# Power_Path_Controllers.net
KiCad netlist of a schematic drawn in Altium Designer
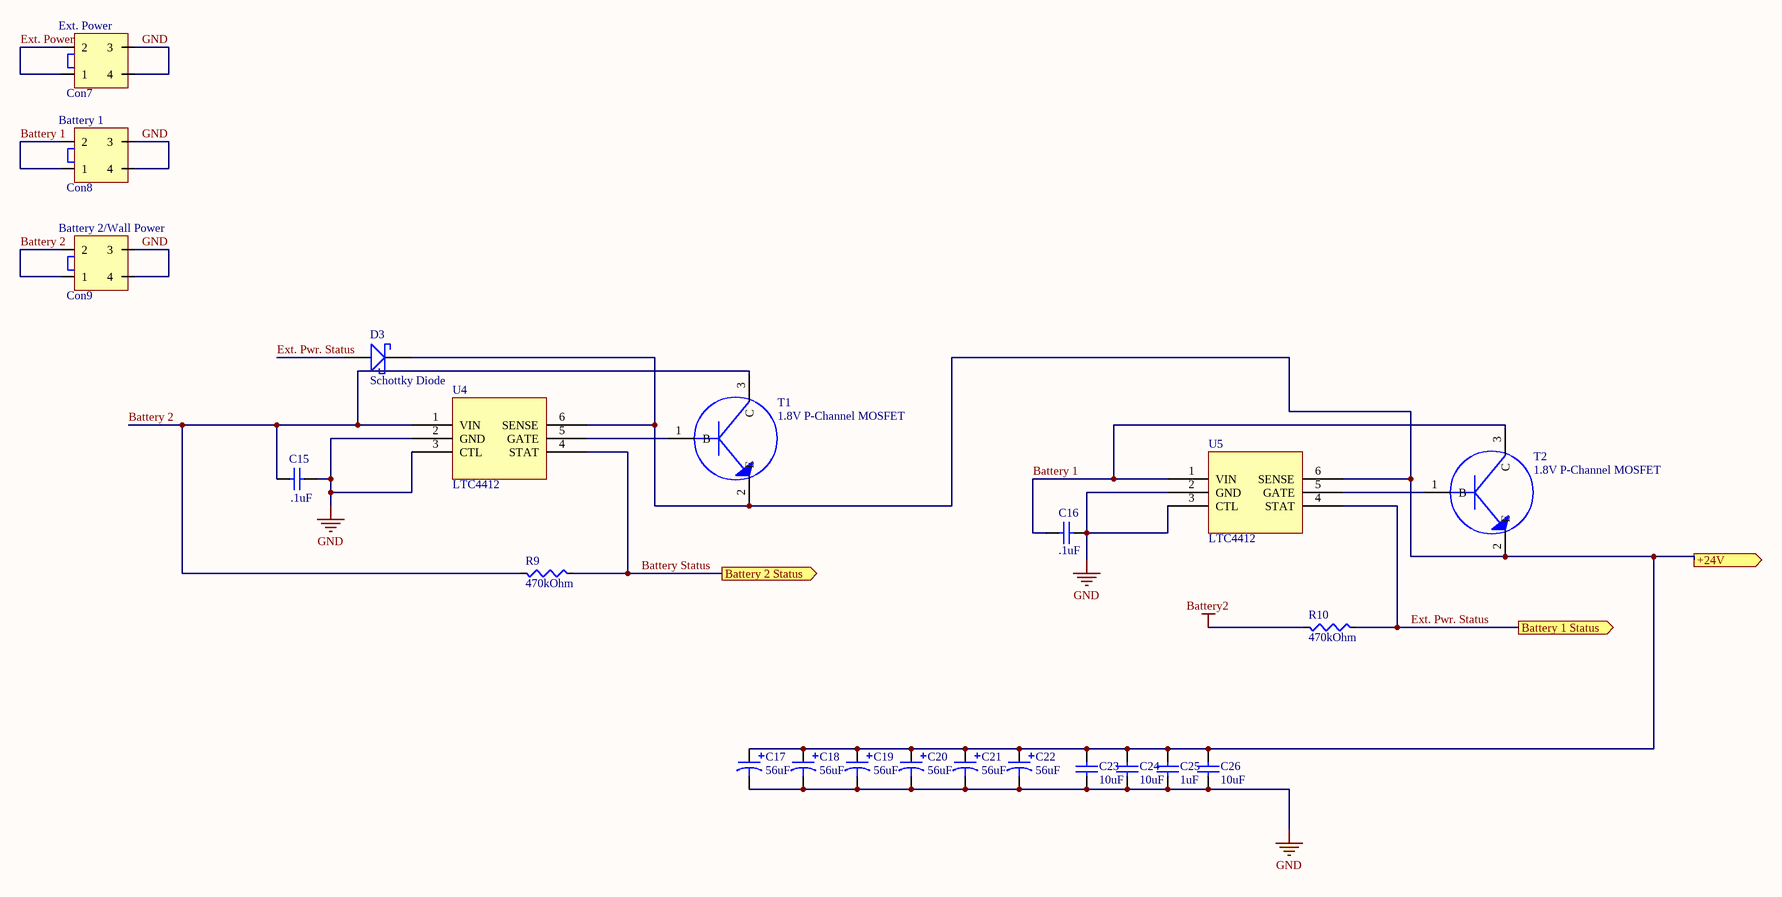
[diagram p0: Power Path Controllers.SchDoc]

(export (version "E")
  (design (tool "Eeschema 10.0.6"))
  (components
    (comp (ref "C15")
      (value ".1uF")
      (footprint "PassiveComponents:0805 (2012) Capacitor")
      (description "Capacitor")
      (libsource (lib "PassiveComponents") (part "Capacitor (non-polarized)"))
    )
    (comp (ref "C16")
      (value ".1uF")
      (footprint "PassiveComponents:0805 (2012) Capacitor")
      (description "Capacitor")
      (libsource (lib "PassiveComponents") (part "Capacitor (non-polarized)"))
    )
    (comp (ref "C17")
      (value "56uF")
      (footprint "PassiveComponents:Radial_8mmDia_SM_E")
      (description "Capacitor (polarized)")
      (libsource (lib "PassiveComponents") (part "Capacitor (polarized)"))
    )
    (comp (ref "C18")
      (value "56uF")
      (footprint "PassiveComponents:Radial_8mmDia_SM_E")
      (description "Capacitor (polarized)")
      (libsource (lib "PassiveComponents") (part "Capacitor (polarized)"))
    )
    (comp (ref "C19")
      (value "56uF")
      (footprint "PassiveComponents:Radial_8mmDia_SM_E")
      (description "Capacitor (polarized)")
      (libsource (lib "PassiveComponents") (part "Capacitor (polarized)"))
    )
    (comp (ref "C20")
      (value "56uF")
      (footprint "PassiveComponents:Radial_8mmDia_SM_E")
      (description "Capacitor (polarized)")
      (libsource (lib "PassiveComponents") (part "Capacitor (polarized)"))
    )
    (comp (ref "C21")
      (value "56uF")
      (footprint "PassiveComponents:Radial_8mmDia_SM_E")
      (description "Capacitor (polarized)")
      (libsource (lib "PassiveComponents") (part "Capacitor (polarized)"))
    )
    (comp (ref "C22")
      (value "56uF")
      (footprint "PassiveComponents:Radial_8mmDia_SM_E")
      (description "Capacitor (polarized)")
      (libsource (lib "PassiveComponents") (part "Capacitor (polarized)"))
    )
    (comp (ref "C23")
      (value "10uF")
      (footprint "PassiveComponents:0805 (2012) Capacitor")
      (description "Capacitor")
      (libsource (lib "PassiveComponents") (part "Capacitor (non-polarized)"))
    )
    (comp (ref "C24")
      (value "10uF")
      (footprint "PassiveComponents:0805 (2012) Capacitor")
      (description "Capacitor")
      (libsource (lib "PassiveComponents") (part "Capacitor (non-polarized)"))
    )
    (comp (ref "C25")
      (value "1uF")
      (footprint "PassiveComponents:0805 (2012) Capacitor")
      (description "Capacitor")
      (libsource (lib "PassiveComponents") (part "Capacitor (non-polarized)"))
    )
    (comp (ref "C26")
      (value "10uF")
      (footprint "PassiveComponents:0805 (2012) Capacitor")
      (description "Capacitor")
      (libsource (lib "PassiveComponents") (part "Capacitor (non-polarized)"))
    )
    (comp (ref "Con7")
      (value "Ext. Power")
      (footprint "Molex:5566-4")
      (libsource (lib "Molex") (part "5566-4"))
    )
    (comp (ref "Con8")
      (value "Battery 1")
      (footprint "Molex:5566-4")
      (libsource (lib "Molex") (part "5566-4"))
    )
    (comp (ref "Con9")
      (value "Battery 2/Wall Power")
      (footprint "Molex:5566-4")
      (libsource (lib "Molex") (part "5566-4"))
    )
    (comp (ref "D3")
      (value "Schottky Diode")
      (footprint "PassiveComponents:DO-41")
      (libsource (lib "PassiveComponents") (part "Schottky Diode"))
    )
    (comp (ref "R9")
      (value "470kOhm")
      (footprint "PassiveComponents:R 0805 (2012) RESISTOR")
      (description "Resistor")
      (libsource (lib "PassiveComponents") (part "Resistor"))
    )
    (comp (ref "R10")
      (value "470kOhm")
      (footprint "PassiveComponents:R 0805 (2012) RESISTOR")
      (description "Resistor")
      (libsource (lib "PassiveComponents") (part "Resistor"))
    )
    (comp (ref "T1")
      (value "1.8V P-Channel MOSFET")
      (footprint "SOT23")
      (libsource (lib "PassiveComponents") (part "Transistor"))
    )
    (comp (ref "T2")
      (value "1.8V P-Channel MOSFET")
      (footprint "SOT23")
      (libsource (lib "PassiveComponents") (part "Transistor"))
    )
    (comp (ref "U4")
      (value "LTC4412")
      (footprint "SOT95P245X110-6N")
      (description "Low Loss Power Path Controller in Thin SOT")
      (libsource (lib "Low Loss Power Path Controller") (part "LTC4412"))
    )
    (comp (ref "U5")
      (value "LTC4412")
      (footprint "SOT95P245X110-6N")
      (description "Low Loss Power Path Controller in Thin SOT")
      (libsource (lib "Low Loss Power Path Controller") (part "LTC4412"))
    )
  )
  (nets
    (net (code "1") (name "/+24V") (class "Default")
      (node (ref "C17") (pin "P") (pinfunction "1_P") (pintype "passive"))
      (node (ref "C18") (pin "P") (pinfunction "1_P") (pintype "passive"))
      (node (ref "C19") (pin "P") (pinfunction "1_P") (pintype "passive"))
      (node (ref "C20") (pin "P") (pinfunction "1_P") (pintype "passive"))
      (node (ref "C21") (pin "P") (pinfunction "1_P") (pintype "passive"))
      (node (ref "C22") (pin "P") (pinfunction "1_P") (pintype "passive"))
      (node (ref "C23") (pin "1") (pinfunction "1_1") (pintype "passive"))
      (node (ref "C24") (pin "1") (pinfunction "1_1") (pintype "passive"))
      (node (ref "C25") (pin "1") (pinfunction "1_1") (pintype "passive"))
      (node (ref "C26") (pin "1") (pinfunction "1_1") (pintype "passive"))
      (node (ref "D3") (pin "K") (pinfunction "K_K") (pintype "passive"))
      (node (ref "T1") (pin "2") (pinfunction "E_2") (pintype "passive"))
      (node (ref "T2") (pin "2") (pinfunction "E_2") (pintype "passive"))
      (node (ref "U4") (pin "6") (pinfunction "SENSE_6") (pintype "passive"))
      (node (ref "U5") (pin "6") (pinfunction "SENSE_6") (pintype "passive"))
    )
    (net (code "2") (name "/Battery 1") (class "Default")
      (node (ref "C16") (pin "1") (pinfunction "1_1") (pintype "passive"))
      (node (ref "Con8") (pin "1") (pinfunction "1_1") (pintype "passive"))
      (node (ref "Con8") (pin "2") (pinfunction "2_2") (pintype "passive"))
      (node (ref "T2") (pin "3") (pinfunction "C_3") (pintype "passive"))
      (node (ref "U5") (pin "1") (pinfunction "VIN_1") (pintype "passive"))
    )
    (net (code "3") (name "/Battery 2") (class "Default")
      (node (ref "C15") (pin "1") (pinfunction "1_1") (pintype "passive"))
      (node (ref "Con9") (pin "1") (pinfunction "1_1") (pintype "passive"))
      (node (ref "Con9") (pin "2") (pinfunction "2_2") (pintype "passive"))
      (node (ref "R9") (pin "2") (pinfunction "2_2") (pintype "passive"))
      (node (ref "T1") (pin "3") (pinfunction "C_3") (pintype "passive"))
      (node (ref "U4") (pin "1") (pinfunction "VIN_1") (pintype "passive"))
    )
    (net (code "4") (name "/Battery Status") (class "Default")
      (node (ref "R9") (pin "1") (pinfunction "1_1") (pintype "passive"))
      (node (ref "U4") (pin "4") (pinfunction "STAT_4") (pintype "passive"))
    )
    (net (code "5") (name "/Ext. Power") (class "Default")
      (node (ref "Con7") (pin "1") (pinfunction "1_1") (pintype "passive"))
      (node (ref "Con7") (pin "2") (pinfunction "2_2") (pintype "passive"))
    )
    (net (code "6") (name "/Ext. Pwr. Status") (class "Default")
      (node (ref "D3") (pin "A") (pinfunction "A_A") (pintype "passive"))
      (node (ref "R10") (pin "1") (pinfunction "1_1") (pintype "passive"))
      (node (ref "U5") (pin "4") (pinfunction "STAT_4") (pintype "passive"))
    )
    (net (code "7") (name "Battery2") (class "Default")
      (node (ref "R10") (pin "2") (pinfunction "2_2") (pintype "passive"))
    )
    (net (code "8") (name "GND") (class "Default")
      (node (ref "C15") (pin "2") (pinfunction "2_2") (pintype "passive"))
      (node (ref "C16") (pin "2") (pinfunction "2_2") (pintype "passive"))
      (node (ref "C17") (pin "N") (pinfunction "2_N") (pintype "passive"))
      (node (ref "C18") (pin "N") (pinfunction "2_N") (pintype "passive"))
      (node (ref "C19") (pin "N") (pinfunction "2_N") (pintype "passive"))
      (node (ref "C20") (pin "N") (pinfunction "2_N") (pintype "passive"))
      (node (ref "C21") (pin "N") (pinfunction "2_N") (pintype "passive"))
      (node (ref "C22") (pin "N") (pinfunction "2_N") (pintype "passive"))
      (node (ref "C23") (pin "2") (pinfunction "2_2") (pintype "passive"))
      (node (ref "C24") (pin "2") (pinfunction "2_2") (pintype "passive"))
      (node (ref "C25") (pin "2") (pinfunction "2_2") (pintype "passive"))
      (node (ref "C26") (pin "2") (pinfunction "2_2") (pintype "passive"))
      (node (ref "Con7") (pin "3") (pinfunction "3_3") (pintype "passive"))
      (node (ref "Con7") (pin "4") (pinfunction "4_4") (pintype "passive"))
      (node (ref "Con8") (pin "3") (pinfunction "3_3") (pintype "passive"))
      (node (ref "Con8") (pin "4") (pinfunction "4_4") (pintype "passive"))
      (node (ref "Con9") (pin "3") (pinfunction "3_3") (pintype "passive"))
      (node (ref "Con9") (pin "4") (pinfunction "4_4") (pintype "passive"))
      (node (ref "U4") (pin "2") (pinfunction "GND_2") (pintype "passive"))
      (node (ref "U4") (pin "3") (pinfunction "CTL_3") (pintype "passive"))
      (node (ref "U5") (pin "2") (pinfunction "GND_2") (pintype "passive"))
      (node (ref "U5") (pin "3") (pinfunction "CTL_3") (pintype "passive"))
    )
    (net (code "9") (name "Net-(T1-B)") (class "Default")
      (node (ref "T1") (pin "1") (pinfunction "B_1") (pintype "passive"))
      (node (ref "U4") (pin "5") (pinfunction "GATE_5") (pintype "passive"))
    )
    (net (code "10") (name "Net-(T2-B)") (class "Default")
      (node (ref "T2") (pin "1") (pinfunction "B_1") (pintype "passive"))
      (node (ref "U5") (pin "5") (pinfunction "GATE_5") (pintype "passive"))
    )
  )
)
